# Wifi.net
KiCad netlist of a schematic drawn in EAGLE
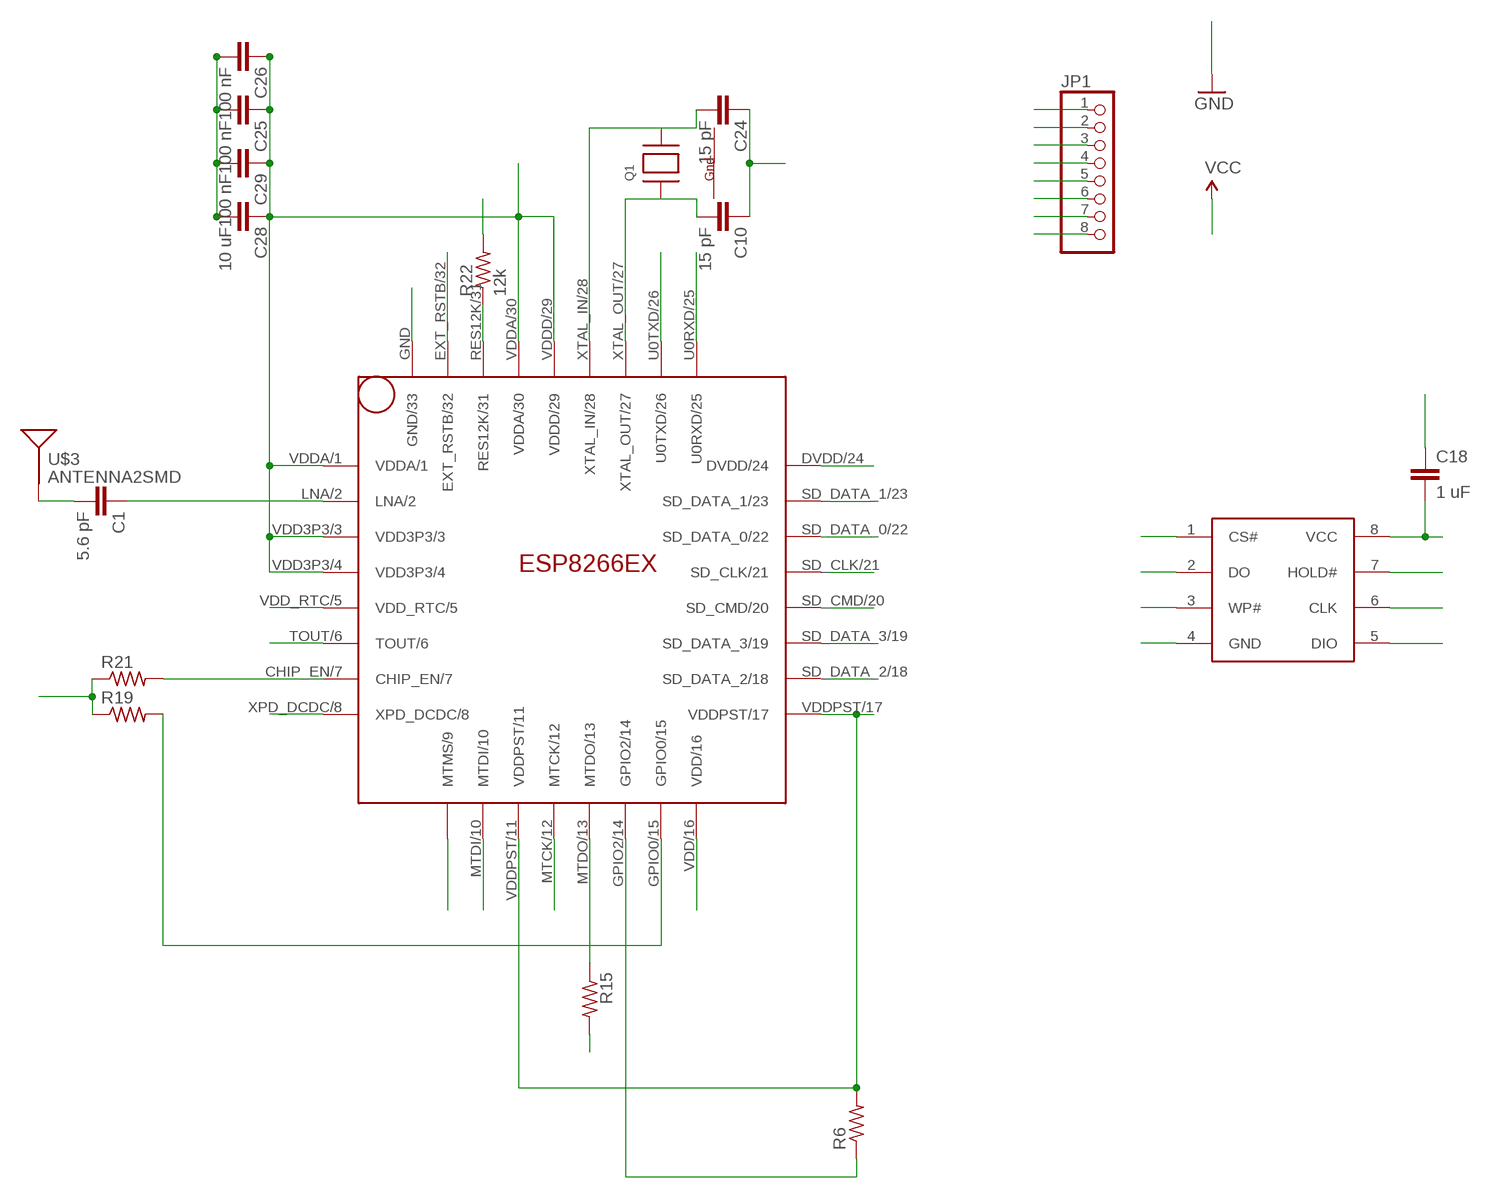
[diagram p0: schematic, sheet 1]

(export (version "E")
  (design (tool "Eeschema 10.0.6"))
  (components
    (comp (ref "C1")
      (value "5.6 pF")
      (footprint "eagle-import:0402-CAP")
      (libsource (lib "eagle-import") (part "CAP0402-CAP"))
    )
    (comp (ref "C10")
      (value "15 pF")
      (footprint "eagle-import:0402-CAP")
      (libsource (lib "eagle-import") (part "CAP0402-CAP"))
    )
    (comp (ref "C18")
      (value "1 uF")
      (footprint "eagle-import:0402-CAP")
      (libsource (lib "eagle-import") (part "CAP0402-CAP"))
    )
    (comp (ref "C24")
      (value "15 pF")
      (footprint "eagle-import:0402-CAP")
      (libsource (lib "eagle-import") (part "CAP0402-CAP"))
    )
    (comp (ref "C25")
      (value "100 nF")
      (footprint "eagle-import:0402-CAP")
      (libsource (lib "eagle-import") (part "CAP0402-CAP"))
    )
    (comp (ref "C26")
      (value "100 nF")
      (footprint "eagle-import:0402-CAP")
      (libsource (lib "eagle-import") (part "CAP0402-CAP"))
    )
    (comp (ref "C28")
      (value "10 uF")
      (footprint "eagle-import:0402-CAP")
      (libsource (lib "eagle-import") (part "CAP0402-CAP"))
    )
    (comp (ref "C29")
      (value "100 nF")
      (footprint "eagle-import:0402-CAP")
      (libsource (lib "eagle-import") (part "CAP0402-CAP"))
    )
    (comp (ref "JP1")
      (value "PINHD-1X8BIG")
      (footprint "eagle-import:1X08-BIG")
      (libsource (lib "eagle-import") (part "PINHD-1X8BIG"))
    )
    (comp (ref "Q1")
      (value "XTAL-4-3225")
      (footprint "eagle-import:NX3225")
      (libsource (lib "eagle-import") (part "XTAL-4-3225"))
    )
    (comp (ref "R6")
      (value "R-US_M0805")
      (footprint "eagle-import:M0805")
      (libsource (lib "eagle-import") (part "R-US_M0805"))
    )
    (comp (ref "R15")
      (value "R-US_M0805")
      (footprint "eagle-import:M0805")
      (libsource (lib "eagle-import") (part "R-US_M0805"))
    )
    (comp (ref "R19")
      (value "R-US_M0805")
      (footprint "eagle-import:M0805")
      (libsource (lib "eagle-import") (part "R-US_M0805"))
    )
    (comp (ref "R21")
      (value "R-US_M0805")
      (footprint "eagle-import:M0805")
      (libsource (lib "eagle-import") (part "R-US_M0805"))
    )
    (comp (ref "R22")
      (value "12k")
      (footprint "eagle-import:M0805")
      (libsource (lib "eagle-import") (part "R-US_M0805"))
    )
    (comp (ref "U$1")
      (value "ESP8266EX")
      (footprint "eagle-import:QFN32")
      (libsource (lib "eagle-import") (part "ESP8266EX"))
    )
    (comp (ref "U$2")
      (value "25Q40")
      (footprint "eagle-import:SOP8")
      (libsource (lib "eagle-import") (part "25Q40"))
    )
    (comp (ref "U$3")
      (value "ANTENNA2SMD")
      (footprint "eagle-import:ANTENNA-CHIP2")
      (libsource (lib "eagle-import") (part "ANTENNA2SMD"))
    )
  )
  (nets
    (net (code "1") (name "/CHIP_EN") (class "Default")
      (node (ref "JP1") (pin "6") (pinfunction "6_6") (pintype "passive"))
      (node (ref "R21") (pin "2") (pinfunction "2_2") (pintype "passive"))
      (node (ref "U$1") (pin "CHIP_EN/7") (pinfunction "CHIP_EN/7_CHIP_EN/7") (pintype "bidirectional"))
    )
    (net (code "2") (name "/CLK") (class "Default")
      (node (ref "U$1") (pin "SD_CLK/21") (pinfunction "SD_CLK/21_SD_CLK/21") (pintype "bidirectional"))
      (node (ref "U$2") (pin "6") (pinfunction "CLK_6") (pintype "bidirectional"))
    )
    (net (code "3") (name "/CS") (class "Default")
      (node (ref "U$1") (pin "SD_CMD/20") (pinfunction "SD_CMD/20_SD_CMD/20") (pintype "bidirectional"))
      (node (ref "U$2") (pin "1") (pinfunction "CS#_1") (pintype "bidirectional"))
    )
    (net (code "4") (name "/G1") (class "Default")
      (node (ref "Q1") (pin "4") (pinfunction "G1_4") (pintype "power_in"))
    )
    (net (code "5") (name "/G2") (class "Default")
      (node (ref "Q1") (pin "2") (pinfunction "G2_2") (pintype "power_in"))
    )
    (net (code "6") (name "/RST") (class "Default")
      (node (ref "JP1") (pin "5") (pinfunction "5_5") (pintype "passive"))
      (node (ref "U$1") (pin "EXT_RSTB/32") (pinfunction "EXT_RSTB/32_EXT_RSTB/32") (pintype "bidirectional"))
    )
    (net (code "7") (name "/RTC") (class "Default")
      (node (ref "JP1") (pin "8") (pinfunction "8_8") (pintype "passive"))
      (node (ref "U$1") (pin "VDD_RTC/5") (pinfunction "VDD_RTC/5_VDD_RTC/5") (pintype "bidirectional"))
    )
    (net (code "8") (name "/RXD") (class "Default")
      (node (ref "JP1") (pin "3") (pinfunction "3_3") (pintype "passive"))
      (node (ref "U$1") (pin "U0RXD/25") (pinfunction "U0RXD/25_U0RXD/25") (pintype "bidirectional"))
    )
    (net (code "9") (name "/SD0") (class "Default")
      (node (ref "U$1") (pin "SD_DATA_0/22") (pinfunction "SD_DATA_0/22_SD_DATA_0/22") (pintype "bidirectional"))
      (node (ref "U$2") (pin "2") (pinfunction "DO_2") (pintype "bidirectional"))
    )
    (net (code "10") (name "/SD1") (class "Default")
      (node (ref "U$1") (pin "SD_DATA_1/23") (pinfunction "SD_DATA_1/23_SD_DATA_1/23") (pintype "bidirectional"))
      (node (ref "U$2") (pin "5") (pinfunction "DIO_5") (pintype "bidirectional"))
    )
    (net (code "11") (name "/SD2") (class "Default")
      (node (ref "U$1") (pin "SD_DATA_2/18") (pinfunction "SD_DATA_2/18_SD_DATA_2/18") (pintype "bidirectional"))
      (node (ref "U$2") (pin "7") (pinfunction "HOLD#_7") (pintype "bidirectional"))
    )
    (net (code "12") (name "/SD3") (class "Default")
      (node (ref "U$1") (pin "SD_DATA_3/19") (pinfunction "SD_DATA_3/19_SD_DATA_3/19") (pintype "bidirectional"))
      (node (ref "U$2") (pin "3") (pinfunction "WP#_3") (pintype "bidirectional"))
    )
    (net (code "13") (name "/TOUT") (class "Default")
      (node (ref "JP1") (pin "7") (pinfunction "7_7") (pintype "passive"))
      (node (ref "U$1") (pin "TOUT/6") (pinfunction "TOUT/6_TOUT/6") (pintype "bidirectional"))
    )
    (net (code "14") (name "/TXD") (class "Default")
      (node (ref "JP1") (pin "4") (pinfunction "4_4") (pintype "passive"))
      (node (ref "U$1") (pin "U0TXD/26") (pinfunction "U0TXD/26_U0TXD/26") (pintype "bidirectional"))
    )
    (net (code "15") (name "/VDD") (class "Default")
      (node (ref "C18") (pin "2") (pinfunction "2_2") (pintype "passive"))
      (node (ref "U$2") (pin "8") (pinfunction "VCC_8") (pintype "bidirectional"))
    )
    (net (code "16") (name "GND") (class "Default")
      (node (ref "C10") (pin "1") (pinfunction "1_1") (pintype "passive"))
      (node (ref "C18") (pin "1") (pinfunction "1_1") (pintype "passive"))
      (node (ref "C24") (pin "1") (pinfunction "1_1") (pintype "passive"))
      (node (ref "JP1") (pin "1") (pinfunction "1_1") (pintype "passive"))
      (node (ref "R15") (pin "2") (pinfunction "2_2") (pintype "passive"))
      (node (ref "R22") (pin "2") (pinfunction "2_2") (pintype "passive"))
      (node (ref "U$1") (pin "GND") (pinfunction "GND/33_GND") (pintype "bidirectional"))
      (node (ref "U$2") (pin "4") (pinfunction "GND_4") (pintype "bidirectional"))
    )
    (net (code "17") (name "Net-(C1-Pad1)") (class "Default")
      (node (ref "C1") (pin "1") (pinfunction "1_1") (pintype "passive"))
      (node (ref "U$1") (pin "LNA/2") (pinfunction "LNA/2_LNA/2") (pintype "bidirectional"))
    )
    (net (code "18") (name "Net-(C25-Pad2)") (class "Default")
      (node (ref "C25") (pin "2") (pinfunction "2_2") (pintype "passive"))
      (node (ref "C26") (pin "2") (pinfunction "2_2") (pintype "passive"))
      (node (ref "C28") (pin "2") (pinfunction "2_2") (pintype "passive"))
      (node (ref "C29") (pin "2") (pinfunction "2_2") (pintype "passive"))
    )
    (net (code "19") (name "Net-(Q1-X1)") (class "Default")
      (node (ref "C10") (pin "2") (pinfunction "2_2") (pintype "passive"))
      (node (ref "Q1") (pin "1") (pinfunction "X1_1") (pintype "bidirectional"))
      (node (ref "U$1") (pin "XTAL_OUT/27") (pinfunction "XTAL_OUT/27_XTAL_OUT/27") (pintype "bidirectional"))
    )
    (net (code "20") (name "Net-(Q1-X2)") (class "Default")
      (node (ref "C24") (pin "2") (pinfunction "2_2") (pintype "passive"))
      (node (ref "Q1") (pin "3") (pinfunction "X2_3") (pintype "bidirectional"))
      (node (ref "U$1") (pin "XTAL_IN/28") (pinfunction "XTAL_IN/28_XTAL_IN/28") (pintype "bidirectional"))
    )
    (net (code "21") (name "Net-(R6-Pad1)") (class "Default")
      (node (ref "R6") (pin "1") (pinfunction "1_1") (pintype "passive"))
      (node (ref "U$1") (pin "GPIO2/14") (pinfunction "GPIO2/14_GPIO2/14") (pintype "bidirectional"))
    )
    (net (code "22") (name "Net-(R6-Pad2)") (class "Default")
      (node (ref "R6") (pin "2") (pinfunction "2_2") (pintype "passive"))
      (node (ref "U$1") (pin "VDDPST/11") (pinfunction "VDDPST/11_VDDPST/11") (pintype "bidirectional"))
      (node (ref "U$1") (pin "VDDPST/17") (pinfunction "VDDPST/17_VDDPST/17") (pintype "bidirectional"))
    )
    (net (code "23") (name "Net-(R15-Pad1)") (class "Default")
      (node (ref "R15") (pin "1") (pinfunction "1_1") (pintype "passive"))
      (node (ref "U$1") (pin "MTDO/13") (pinfunction "MTDO/13_MTDO/13") (pintype "bidirectional"))
    )
    (net (code "24") (name "Net-(R19-Pad2)") (class "Default")
      (node (ref "R19") (pin "2") (pinfunction "2_2") (pintype "passive"))
      (node (ref "U$1") (pin "GPIO0/15") (pinfunction "GPIO0/15_GPIO0/15") (pintype "bidirectional"))
    )
    (net (code "25") (name "Net-(R22-Pad1)") (class "Default")
      (node (ref "R22") (pin "1") (pinfunction "1_1") (pintype "passive"))
      (node (ref "U$1") (pin "RES12K/31") (pinfunction "RES12K/31_RES12K/31") (pintype "bidirectional"))
    )
    (net (code "26") (name "Net-(U$3-SIGNAL)") (class "Default")
      (node (ref "C1") (pin "2") (pinfunction "2_2") (pintype "passive"))
      (node (ref "U$3") (pin "FEED") (pinfunction "SIGNAL_FEED") (pintype "bidirectional"))
    )
    (net (code "27") (name "VCC") (class "Default")
      (node (ref "C25") (pin "1") (pinfunction "1_1") (pintype "passive"))
      (node (ref "C26") (pin "1") (pinfunction "1_1") (pintype "passive"))
      (node (ref "C28") (pin "1") (pinfunction "1_1") (pintype "passive"))
      (node (ref "C29") (pin "1") (pinfunction "1_1") (pintype "passive"))
      (node (ref "JP1") (pin "2") (pinfunction "2_2") (pintype "passive"))
      (node (ref "R19") (pin "1") (pinfunction "1_1") (pintype "passive"))
      (node (ref "R21") (pin "1") (pinfunction "1_1") (pintype "passive"))
      (node (ref "U$1") (pin "VDD3P3/3") (pinfunction "VDD3P3/3_VDD3P3/3") (pintype "bidirectional"))
      (node (ref "U$1") (pin "VDD3P3/4") (pinfunction "VDD3P3/4_VDD3P3/4") (pintype "bidirectional"))
      (node (ref "U$1") (pin "VDDA/1") (pinfunction "VDDA/1_VDDA/1") (pintype "bidirectional"))
      (node (ref "U$1") (pin "VDDA/30") (pinfunction "VDDA/30_VDDA/30") (pintype "bidirectional"))
      (node (ref "U$1") (pin "VDDD/29") (pinfunction "VDDD/29_VDDD/29") (pintype "bidirectional"))
    )
    (net (code "28") (name "unconnected-(U$1-PadDVDD{slash}24)") (class "Default")
      (node (ref "U$1") (pin "DVDD/24") (pinfunction "DVDD/24_DVDD/24") (pintype "bidirectional"))
    )
    (net (code "29") (name "unconnected-(U$1-PadMTCK{slash}12)") (class "Default")
      (node (ref "U$1") (pin "MTCK/12") (pinfunction "MTCK/12_MTCK/12") (pintype "bidirectional"))
    )
    (net (code "30") (name "unconnected-(U$1-PadMTDI{slash}10)") (class "Default")
      (node (ref "U$1") (pin "MTDI/10") (pinfunction "MTDI/10_MTDI/10") (pintype "bidirectional"))
    )
    (net (code "31") (name "unconnected-(U$1-PadMTMS{slash}9)") (class "Default")
      (node (ref "U$1") (pin "MTMS/9") (pinfunction "MTMS/9_MTMS/9") (pintype "bidirectional"))
    )
    (net (code "32") (name "unconnected-(U$1-PadVDD{slash}16)") (class "Default")
      (node (ref "U$1") (pin "VDD/16") (pinfunction "VDD/16_VDD/16") (pintype "bidirectional"))
    )
    (net (code "33") (name "unconnected-(U$1-PadXPD_DCDC{slash}8)") (class "Default")
      (node (ref "U$1") (pin "XPD_DCDC/8") (pinfunction "XPD_DCDC/8_XPD_DCDC/8") (pintype "bidirectional"))
    )
  )
)
